# TI_ADC_VOLTAGE.net
KiCad netlist of a schematic drawn in Altium Designer
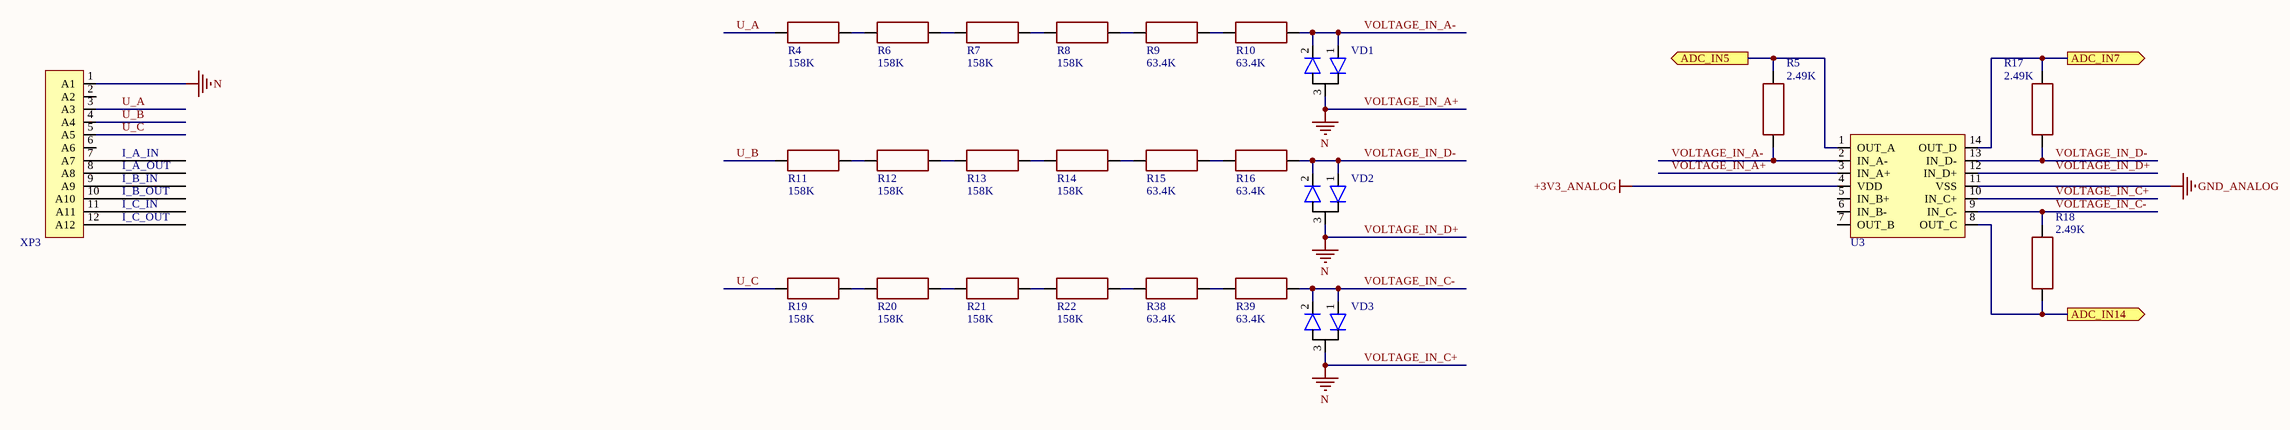
[diagram p0: TI_ADC_VOLTAGE.SchDoc]

(export (version "E")
  (design (tool "Eeschema 10.0.6"))
  (components
    (comp (ref "R4")
      (value "158K")
      (footprint "RES: 0603")
      (fields
        (field (name "POWER") "0.1W")
        (field (name "TOLERANCE") "±5%")
        (field (name "Comment") "Resistor_0603")
      )
      (libsource (lib "resistor") (part "Resistor_0603"))
    )
    (comp (ref "R5")
      (value "2.49K")
      (footprint "RES: 0603")
      (fields
        (field (name "POWER") "0.1W")
        (field (name "TOLERANCE") "±5%")
        (field (name "Comment") "Resistor_0603")
      )
      (libsource (lib "") (part "Resistor_0603_1"))
    )
    (comp (ref "R6")
      (value "158K")
      (footprint "RES: 0603")
      (fields
        (field (name "POWER") "0.1W")
        (field (name "TOLERANCE") "±5%")
        (field (name "Comment") "Resistor_0603")
      )
      (libsource (lib "resistor") (part "Resistor_0603"))
    )
    (comp (ref "R7")
      (value "158K")
      (footprint "RES: 0603")
      (fields
        (field (name "POWER") "0.1W")
        (field (name "TOLERANCE") "±5%")
        (field (name "Comment") "Resistor_0603")
      )
      (libsource (lib "resistor") (part "Resistor_0603"))
    )
    (comp (ref "R8")
      (value "158K")
      (footprint "RES: 0603")
      (fields
        (field (name "POWER") "0.1W")
        (field (name "TOLERANCE") "±5%")
        (field (name "Comment") "Resistor_0603")
      )
      (libsource (lib "resistor") (part "Resistor_0603"))
    )
    (comp (ref "R9")
      (value "63.4K")
      (footprint "RES: 0603")
      (fields
        (field (name "POWER") "0.1W")
        (field (name "TOLERANCE") "±5%")
        (field (name "Comment") "Resistor_0603")
      )
      (libsource (lib "resistor") (part "Resistor_0603"))
    )
    (comp (ref "R10")
      (value "63.4K")
      (footprint "RES: 0603")
      (fields
        (field (name "POWER") "0.1W")
        (field (name "TOLERANCE") "±5%")
        (field (name "Comment") "Resistor_0603")
      )
      (libsource (lib "resistor") (part "Resistor_0603"))
    )
    (comp (ref "R11")
      (value "158K")
      (footprint "RES: 0603")
      (fields
        (field (name "POWER") "0.1W")
        (field (name "TOLERANCE") "±5%")
        (field (name "Comment") "Resistor_0603")
      )
      (libsource (lib "resistor") (part "Resistor_0603"))
    )
    (comp (ref "R12")
      (value "158K")
      (footprint "RES: 0603")
      (fields
        (field (name "POWER") "0.1W")
        (field (name "TOLERANCE") "±5%")
        (field (name "Comment") "Resistor_0603")
      )
      (libsource (lib "resistor") (part "Resistor_0603"))
    )
    (comp (ref "R13")
      (value "158K")
      (footprint "RES: 0603")
      (fields
        (field (name "POWER") "0.1W")
        (field (name "TOLERANCE") "±5%")
        (field (name "Comment") "Resistor_0603")
      )
      (libsource (lib "resistor") (part "Resistor_0603"))
    )
    (comp (ref "R14")
      (value "158K")
      (footprint "RES: 0603")
      (fields
        (field (name "POWER") "0.1W")
        (field (name "TOLERANCE") "±5%")
        (field (name "Comment") "Resistor_0603")
      )
      (libsource (lib "resistor") (part "Resistor_0603"))
    )
    (comp (ref "R15")
      (value "63.4K")
      (footprint "RES: 0603")
      (fields
        (field (name "POWER") "0.1W")
        (field (name "TOLERANCE") "±5%")
        (field (name "Comment") "Resistor_0603")
      )
      (libsource (lib "resistor") (part "Resistor_0603"))
    )
    (comp (ref "R16")
      (value "63.4K")
      (footprint "RES: 0603")
      (fields
        (field (name "POWER") "0.1W")
        (field (name "TOLERANCE") "±5%")
        (field (name "Comment") "Resistor_0603")
      )
      (libsource (lib "resistor") (part "Resistor_0603"))
    )
    (comp (ref "R17")
      (value "2.49K")
      (footprint "RES: 0603")
      (fields
        (field (name "POWER") "0.1W")
        (field (name "TOLERANCE") "±5%")
        (field (name "Comment") "Resistor_0603")
      )
      (libsource (lib "") (part "Resistor_0603_1"))
    )
    (comp (ref "R18")
      (value "2.49K")
      (footprint "RES: 0603")
      (fields
        (field (name "POWER") "0.1W")
        (field (name "TOLERANCE") "±5%")
        (field (name "Comment") "Resistor_0603")
      )
      (libsource (lib "") (part "Resistor_0603_1"))
    )
    (comp (ref "R19")
      (value "158K")
      (footprint "RES: 0603")
      (fields
        (field (name "POWER") "0.1W")
        (field (name "TOLERANCE") "±5%")
        (field (name "Comment") "Resistor_0603")
      )
      (libsource (lib "resistor") (part "Resistor_0603"))
    )
    (comp (ref "R20")
      (value "158K")
      (footprint "RES: 0603")
      (fields
        (field (name "POWER") "0.1W")
        (field (name "TOLERANCE") "±5%")
        (field (name "Comment") "Resistor_0603")
      )
      (libsource (lib "resistor") (part "Resistor_0603"))
    )
    (comp (ref "R21")
      (value "158K")
      (footprint "RES: 0603")
      (fields
        (field (name "POWER") "0.1W")
        (field (name "TOLERANCE") "±5%")
        (field (name "Comment") "Resistor_0603")
      )
      (libsource (lib "resistor") (part "Resistor_0603"))
    )
    (comp (ref "R22")
      (value "158K")
      (footprint "RES: 0603")
      (fields
        (field (name "POWER") "0.1W")
        (field (name "TOLERANCE") "±5%")
        (field (name "Comment") "Resistor_0603")
      )
      (libsource (lib "resistor") (part "Resistor_0603"))
    )
    (comp (ref "R38")
      (value "63.4K")
      (footprint "RES: 0603")
      (fields
        (field (name "POWER") "0.1W")
        (field (name "TOLERANCE") "±5%")
        (field (name "Comment") "Resistor_0603")
      )
      (libsource (lib "resistor") (part "Resistor_0603"))
    )
    (comp (ref "R39")
      (value "63.4K")
      (footprint "RES: 0603")
      (fields
        (field (name "POWER") "0.1W")
        (field (name "TOLERANCE") "±5%")
        (field (name "Comment") "Resistor_0603")
      )
      (libsource (lib "resistor") (part "Resistor_0603"))
    )
    (comp (ref "U3")
      (value "MCP6004")
      (footprint "SOIC-14")
      (description "1 MHz, Low-Power Op Amp")
      (fields (field (name "MANUFACTURER") "Microchip"))
      (libsource (lib "MY_INT_LIB") (part "MCP6004"))
    )
    (comp (ref "VD1")
      (value "BAV99")
      (footprint "SOT-23-3")
      (description "High-speed switching diode")
      (fields (field (name "MANUFACTURER") "Nexperia"))
      (libsource (lib "MY_INT_LIB") (part "BAV99"))
    )
    (comp (ref "VD2")
      (value "BAV99")
      (footprint "SOT-23-3")
      (description "High-speed switching diode")
      (fields (field (name "MANUFACTURER") "Nexperia"))
      (libsource (lib "MY_INT_LIB") (part "BAV99"))
    )
    (comp (ref "VD3")
      (value "BAV99")
      (footprint "SOT-23-3")
      (description "High-speed switching diode")
      (fields (field (name "MANUFACTURER") "Nexperia"))
      (libsource (lib "MY_INT_LIB") (part "BAV99"))
    )
    (comp (ref "XP3")
      (value "PLS-6 (DS1MSTB 2,5/12-GF-5,08021-1x6)")
      (footprint "MSTB 2,5/12-GF-5,08")
      (description "Surface Mount, Single row, 12 Positions, 5.08mm")
      (fields (field (name "MANUFACTURER") "Phoenix contact"))
      (libsource (lib "MY_INT_LIB") (part "MSTB 2,5/12-GF-5,08"))
    )
  )
  (nets
    (net (code "1") (name "+3V3_ANALOG") (class "Default")
      (node (ref "U3") (pin "4") (pinfunction "VDD_4") (pintype "power_in"))
    )
    (net (code "2") (name "/ADC_IN5") (class "Default")
      (node (ref "R5") (pin "2") (pinfunction "2_2") (pintype "passive"))
      (node (ref "U3") (pin "1") (pinfunction "OUT_A_1") (pintype "passive"))
    )
    (net (code "3") (name "/ADC_IN7") (class "Default")
      (node (ref "R17") (pin "2") (pinfunction "2_2") (pintype "passive"))
      (node (ref "U3") (pin "14") (pinfunction "OUT_D_14") (pintype "passive"))
    )
    (net (code "4") (name "/ADC_IN14") (class "Default")
      (node (ref "R18") (pin "1") (pinfunction "1_1") (pintype "passive"))
      (node (ref "U3") (pin "8") (pinfunction "OUT_C_8") (pintype "passive"))
    )
    (net (code "5") (name "/U_A") (class "Default")
      (node (ref "R4") (pin "1") (pinfunction "1_1") (pintype "passive"))
      (node (ref "XP3") (pin "3") (pinfunction "A3_3") (pintype "passive"))
    )
    (net (code "6") (name "/U_B") (class "Default")
      (node (ref "R11") (pin "1") (pinfunction "1_1") (pintype "passive"))
      (node (ref "XP3") (pin "4") (pinfunction "A4_4") (pintype "passive"))
    )
    (net (code "7") (name "/U_C") (class "Default")
      (node (ref "R19") (pin "1") (pinfunction "1_1") (pintype "passive"))
      (node (ref "XP3") (pin "5") (pinfunction "A5_5") (pintype "passive"))
    )
    (net (code "8") (name "/VOLTAGE_IN_A-") (class "Default")
      (node (ref "R10") (pin "2") (pinfunction "2_2") (pintype "passive"))
      (node (ref "R5") (pin "1") (pinfunction "1_1") (pintype "passive"))
      (node (ref "U3") (pin "2") (pinfunction "IN_A-_2") (pintype "passive"))
      (node (ref "VD1") (pin "1") (pintype "passive"))
      (node (ref "VD1") (pin "2") (pintype "passive"))
    )
    (net (code "9") (name "/VOLTAGE_IN_C-") (class "Default")
      (node (ref "R18") (pin "2") (pinfunction "2_2") (pintype "passive"))
      (node (ref "R39") (pin "2") (pinfunction "2_2") (pintype "passive"))
      (node (ref "U3") (pin "9") (pinfunction "IN_C-_9") (pintype "passive"))
      (node (ref "VD3") (pin "1") (pintype "passive"))
      (node (ref "VD3") (pin "2") (pintype "passive"))
    )
    (net (code "10") (name "/VOLTAGE_IN_D-") (class "Default")
      (node (ref "R16") (pin "2") (pinfunction "2_2") (pintype "passive"))
      (node (ref "R17") (pin "1") (pinfunction "1_1") (pintype "passive"))
      (node (ref "U3") (pin "13") (pinfunction "IN_D-_13") (pintype "passive"))
      (node (ref "VD2") (pin "1") (pintype "passive"))
      (node (ref "VD2") (pin "2") (pintype "passive"))
    )
    (net (code "11") (name "GND_ANALOG") (class "Default")
      (node (ref "U3") (pin "11") (pinfunction "VSS_11") (pintype "power_in"))
    )
    (net (code "12") (name "N") (class "Default")
      (node (ref "U3") (pin "10") (pinfunction "IN_C+_10") (pintype "passive"))
      (node (ref "U3") (pin "12") (pinfunction "IN_D+_12") (pintype "passive"))
      (node (ref "U3") (pin "3") (pinfunction "IN_A+_3") (pintype "passive"))
      (node (ref "VD1") (pin "3") (pintype "passive"))
      (node (ref "VD2") (pin "3") (pintype "passive"))
      (node (ref "VD3") (pin "3") (pintype "passive"))
      (node (ref "XP3") (pin "1") (pinfunction "A1_1") (pintype "passive"))
    )
    (net (code "13") (name "Net-(R4-Pad2)") (class "Default")
      (node (ref "R4") (pin "2") (pinfunction "2_2") (pintype "passive"))
      (node (ref "R6") (pin "1") (pinfunction "1_1") (pintype "passive"))
    )
    (net (code "14") (name "Net-(R6-Pad2)") (class "Default")
      (node (ref "R6") (pin "2") (pinfunction "2_2") (pintype "passive"))
      (node (ref "R7") (pin "1") (pinfunction "1_1") (pintype "passive"))
    )
    (net (code "15") (name "Net-(R7-Pad2)") (class "Default")
      (node (ref "R7") (pin "2") (pinfunction "2_2") (pintype "passive"))
      (node (ref "R8") (pin "1") (pinfunction "1_1") (pintype "passive"))
    )
    (net (code "16") (name "Net-(R8-Pad2)") (class "Default")
      (node (ref "R8") (pin "2") (pinfunction "2_2") (pintype "passive"))
      (node (ref "R9") (pin "1") (pinfunction "1_1") (pintype "passive"))
    )
    (net (code "17") (name "Net-(R10-Pad1)") (class "Default")
      (node (ref "R10") (pin "1") (pinfunction "1_1") (pintype "passive"))
      (node (ref "R9") (pin "2") (pinfunction "2_2") (pintype "passive"))
    )
    (net (code "18") (name "Net-(R11-Pad2)") (class "Default")
      (node (ref "R11") (pin "2") (pinfunction "2_2") (pintype "passive"))
      (node (ref "R12") (pin "1") (pinfunction "1_1") (pintype "passive"))
    )
    (net (code "19") (name "Net-(R12-Pad2)") (class "Default")
      (node (ref "R12") (pin "2") (pinfunction "2_2") (pintype "passive"))
      (node (ref "R13") (pin "1") (pinfunction "1_1") (pintype "passive"))
    )
    (net (code "20") (name "Net-(R13-Pad2)") (class "Default")
      (node (ref "R13") (pin "2") (pinfunction "2_2") (pintype "passive"))
      (node (ref "R14") (pin "1") (pinfunction "1_1") (pintype "passive"))
    )
    (net (code "21") (name "Net-(R14-Pad2)") (class "Default")
      (node (ref "R14") (pin "2") (pinfunction "2_2") (pintype "passive"))
      (node (ref "R15") (pin "1") (pinfunction "1_1") (pintype "passive"))
    )
    (net (code "22") (name "Net-(R15-Pad2)") (class "Default")
      (node (ref "R15") (pin "2") (pinfunction "2_2") (pintype "passive"))
      (node (ref "R16") (pin "1") (pinfunction "1_1") (pintype "passive"))
    )
    (net (code "23") (name "Net-(R19-Pad2)") (class "Default")
      (node (ref "R19") (pin "2") (pinfunction "2_2") (pintype "passive"))
      (node (ref "R20") (pin "1") (pinfunction "1_1") (pintype "passive"))
    )
    (net (code "24") (name "Net-(R20-Pad2)") (class "Default")
      (node (ref "R20") (pin "2") (pinfunction "2_2") (pintype "passive"))
      (node (ref "R21") (pin "1") (pinfunction "1_1") (pintype "passive"))
    )
    (net (code "25") (name "Net-(R21-Pad2)") (class "Default")
      (node (ref "R21") (pin "2") (pinfunction "2_2") (pintype "passive"))
      (node (ref "R22") (pin "1") (pinfunction "1_1") (pintype "passive"))
    )
    (net (code "26") (name "Net-(R22-Pad2)") (class "Default")
      (node (ref "R22") (pin "2") (pinfunction "2_2") (pintype "passive"))
      (node (ref "R38") (pin "1") (pinfunction "1_1") (pintype "passive"))
    )
    (net (code "27") (name "Net-(R38-Pad2)") (class "Default")
      (node (ref "R38") (pin "2") (pinfunction "2_2") (pintype "passive"))
      (node (ref "R39") (pin "1") (pinfunction "1_1") (pintype "passive"))
    )
    (net (code "28") (name "unconnected-(U3-IN_B+-Pad5)") (class "Default")
      (node (ref "U3") (pin "5") (pinfunction "IN_B+_5") (pintype "passive"))
    )
    (net (code "29") (name "unconnected-(U3-IN_B--Pad6)") (class "Default")
      (node (ref "U3") (pin "6") (pinfunction "IN_B-_6") (pintype "passive"))
    )
    (net (code "30") (name "unconnected-(U3-OUT_B-Pad7)") (class "Default")
      (node (ref "U3") (pin "7") (pinfunction "OUT_B_7") (pintype "passive"))
    )
    (net (code "31") (name "unconnected-(XP3-A2-Pad2)") (class "Default")
      (node (ref "XP3") (pin "2") (pinfunction "A2_2") (pintype "passive"))
    )
    (net (code "32") (name "unconnected-(XP3-A6-Pad6)") (class "Default")
      (node (ref "XP3") (pin "6") (pinfunction "A6_6") (pintype "passive"))
    )
    (net (code "33") (name "unconnected-(XP3-A7-Pad7)") (class "Default")
      (node (ref "XP3") (pin "7") (pinfunction "A7_7") (pintype "passive"))
    )
    (net (code "34") (name "unconnected-(XP3-A8-Pad8)") (class "Default")
      (node (ref "XP3") (pin "8") (pinfunction "A8_8") (pintype "passive"))
    )
    (net (code "35") (name "unconnected-(XP3-A9-Pad9)") (class "Default")
      (node (ref "XP3") (pin "9") (pinfunction "A9_9") (pintype "passive"))
    )
    (net (code "36") (name "unconnected-(XP3-A10-Pad10)") (class "Default")
      (node (ref "XP3") (pin "10") (pinfunction "A10_10") (pintype "passive"))
    )
    (net (code "37") (name "unconnected-(XP3-A11-Pad11)") (class "Default")
      (node (ref "XP3") (pin "11") (pinfunction "A11_11") (pintype "passive"))
    )
    (net (code "38") (name "unconnected-(XP3-A12-Pad12)") (class "Default")
      (node (ref "XP3") (pin "12") (pinfunction "A12_12") (pintype "passive"))
    )
  )
)
